# EDU_High-Speed-Design_Connectors.net
KiCad netlist of a schematic drawn in Altium Designer
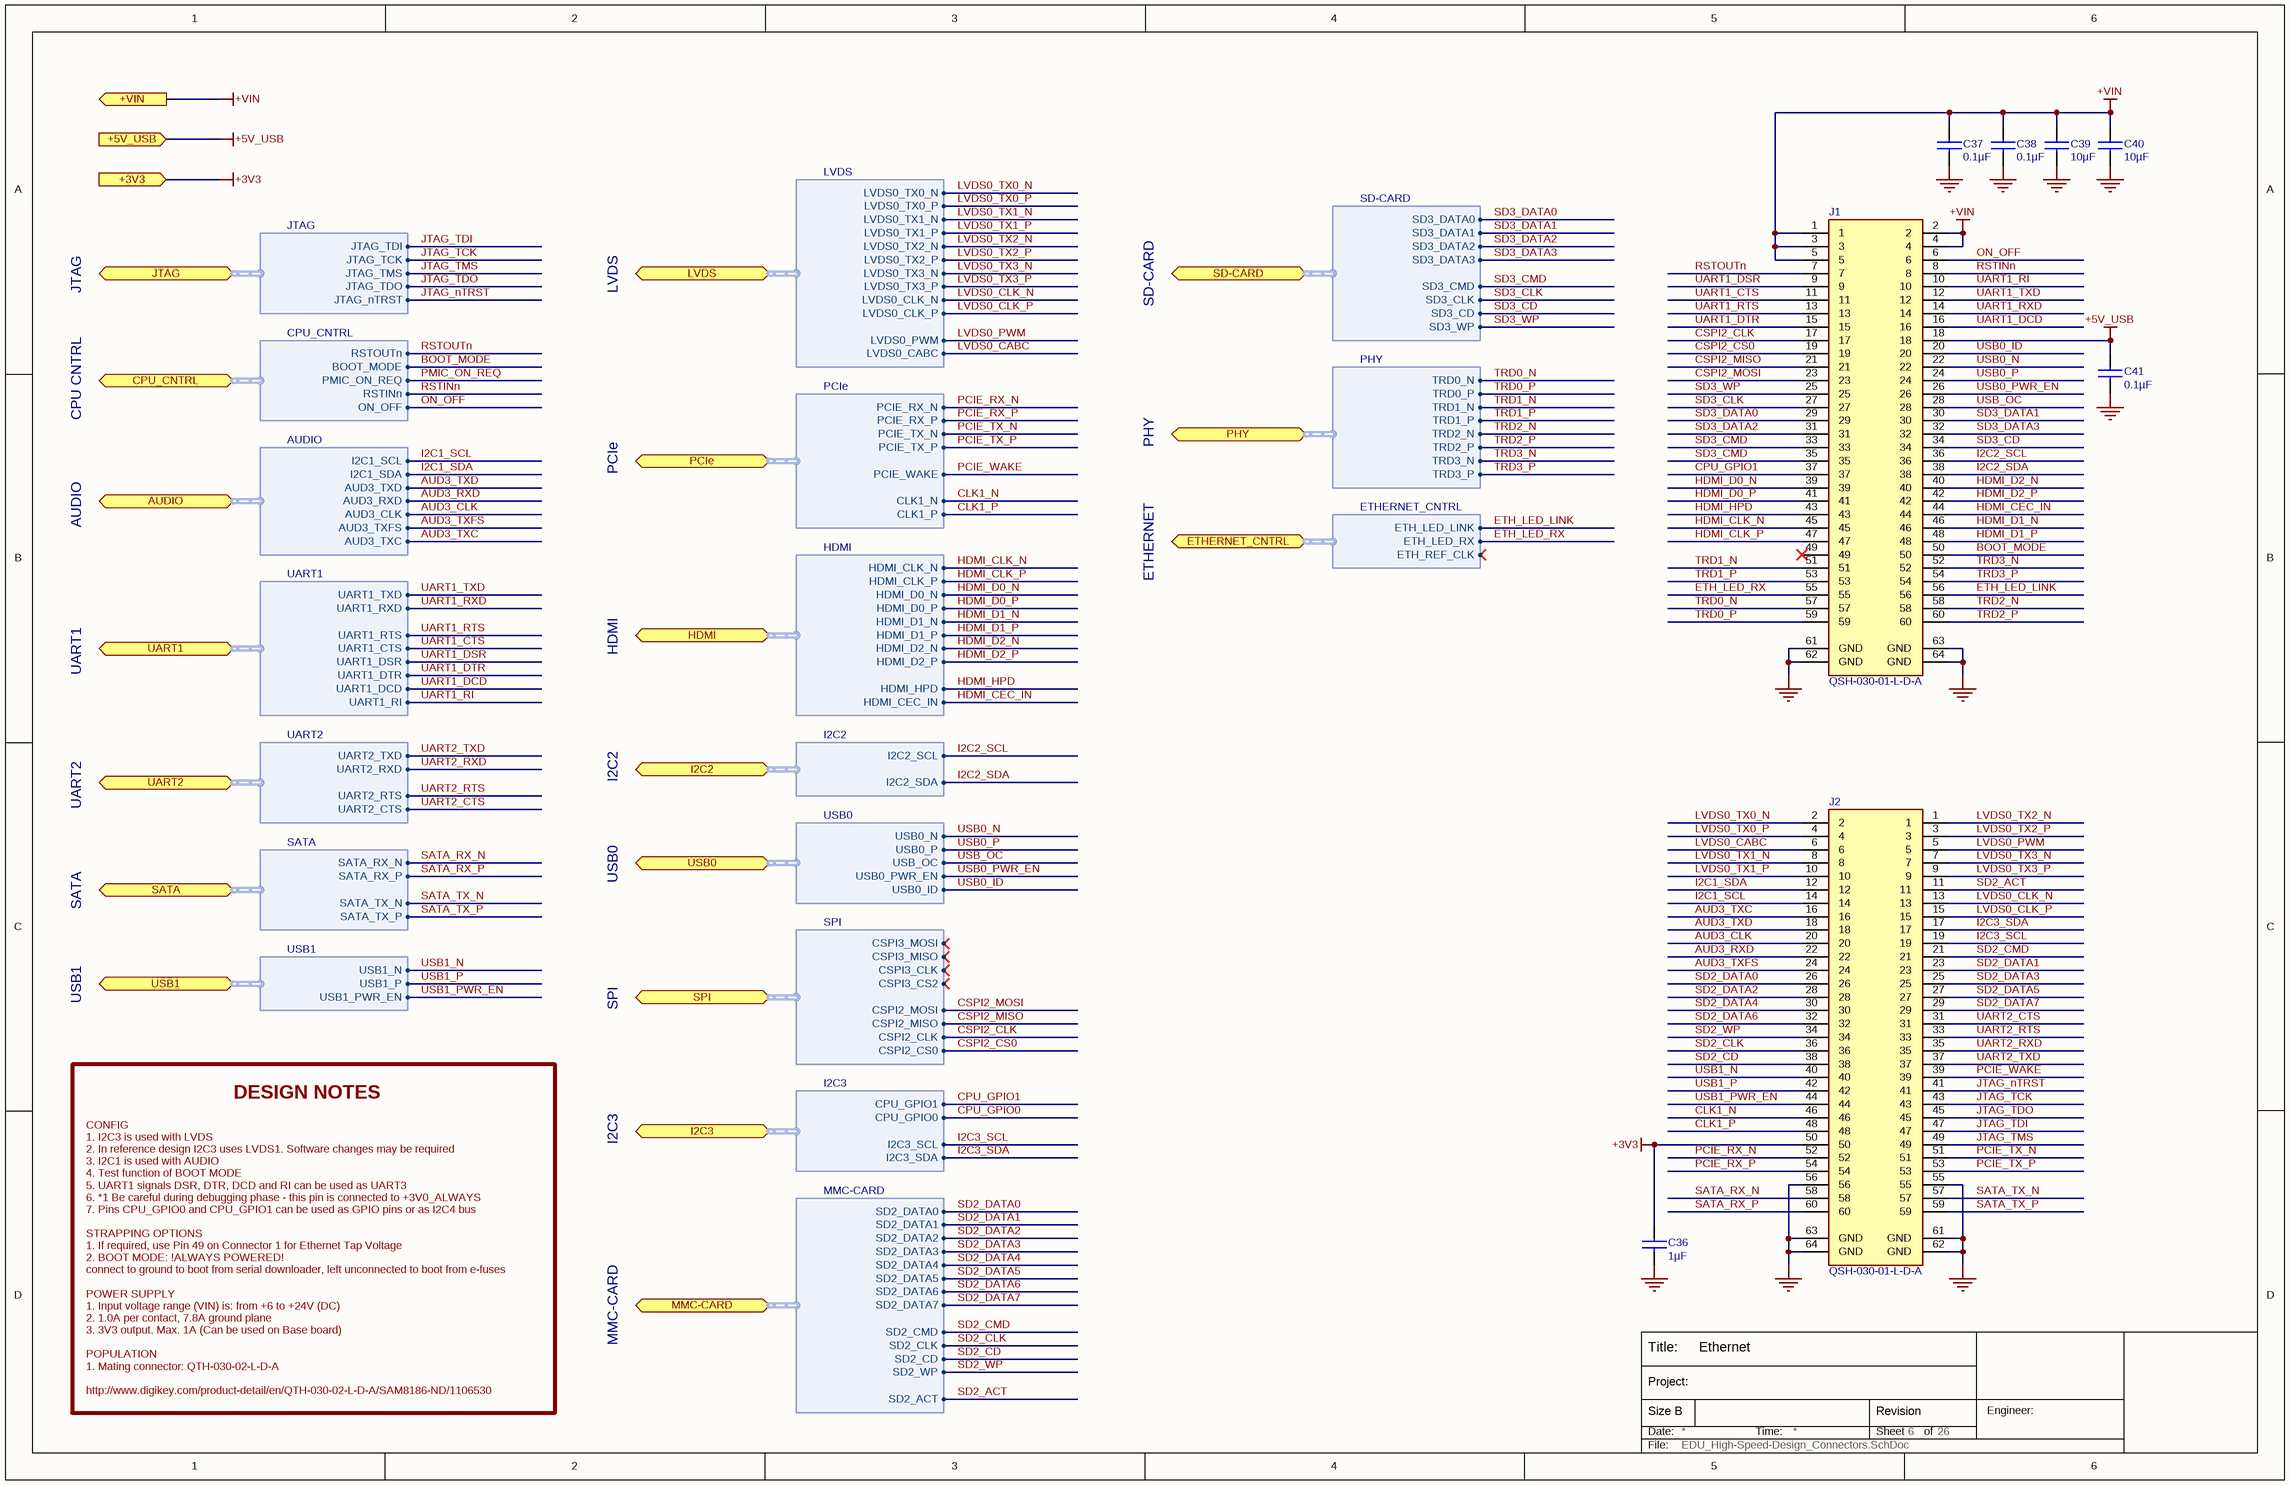
[diagram p0: EDU_High-Speed-Design_Connectors.SchDoc]

(export (version "E")
  (design (tool "Eeschema 10.0.6"))
  (components
    (comp (ref "C36")
      (value "1µF")
      (footprint "C0402")
      (description "CAP CER 1.0UF 16V X5R 0402")
      (fields (field (name "VOLTAGE") "16V"))
      (libsource (lib "EDU_High-Speed-Design") (part "C1005X5R1C105K"))
    )
    (comp (ref "C37")
      (value "0.1µF")
      (footprint "C0402")
      (description "CAP CER .10UF 50V X5R 10% 0402")
      (fields (field (name "VOLTAGE") "50V"))
      (libsource (lib "EDU_High-Speed-Design") (part "C1005X5R1H104K"))
    )
    (comp (ref "C38")
      (value "0.1µF")
      (footprint "C0402")
      (description "CAP CER .10UF 50V X5R 10% 0402")
      (fields (field (name "VOLTAGE") "50V"))
      (libsource (lib "EDU_High-Speed-Design") (part "C1005X5R1H104K"))
    )
    (comp (ref "C39")
      (value "10µF")
      (footprint "C1206")
      (description "CAP CER 10UF 35V X5R 1206")
      (fields (field (name "VOLTAGE") "35V"))
      (libsource (lib "EDU_High-Speed-Design") (part "GRM31CR6YA106KA12L"))
    )
    (comp (ref "C40")
      (value "10µF")
      (footprint "C1206")
      (description "CAP CER 10UF 35V X5R 1206")
      (fields (field (name "VOLTAGE") "35V"))
      (libsource (lib "EDU_High-Speed-Design") (part "GRM31CR6YA106KA12L"))
    )
    (comp (ref "C41")
      (value "0.1µF")
      (footprint "C0402")
      (description "CAP CER .10UF 50V X5R 10% 0402")
      (fields (field (name "VOLTAGE") "50V"))
      (libsource (lib "EDU_High-Speed-Design") (part "C1005X5R1H104K"))
    )
    (comp (ref "J1")
      (value "QSH-030-01-L-D-A")
      (footprint "QSH-030-01-L-D-A")
      (description "CONN RCPT HI-SPD .5MM 60POS DL")
      (libsource (lib "") (part "QSH-030-01-L-D-A_1"))
    )
    (comp (ref "J2")
      (value "QSH-030-01-L-D-A")
      (footprint "QSH-030-01-L-D-A")
      (description "CONN RCPT HI-SPD .5MM 60POS DL")
      (libsource (lib "EDU_High-Speed-Design") (part "QSH-030-01-L-D-A"))
    )
  )
  (nets
    (net (code "19") (name "+3V3") (class "Default")
      (node (ref "C36") (pin "1") (pinfunction "1_1") (pintype "passive"))
      (node (ref "J2") (pin "50") (pinfunction "50_50") (pintype "passive"))
    )
    (net (code "20") (name "+5V_USB") (class "Default")
      (node (ref "C41") (pin "1") (pinfunction "1_1") (pintype "passive"))
      (node (ref "J1") (pin "18") (pinfunction "18_18") (pintype "passive"))
    )
    (net (code "21") (name "+VIN") (class "Default")
      (node (ref "C37") (pin "1") (pinfunction "1_1") (pintype "passive"))
      (node (ref "C38") (pin "1") (pinfunction "1_1") (pintype "passive"))
      (node (ref "C39") (pin "1") (pinfunction "1_1") (pintype "passive"))
      (node (ref "C40") (pin "1") (pinfunction "1_1") (pintype "passive"))
      (node (ref "J1") (pin "1") (pinfunction "1_1") (pintype "passive"))
      (node (ref "J1") (pin "2") (pinfunction "2_2") (pintype "passive"))
      (node (ref "J1") (pin "3") (pinfunction "3_3") (pintype "passive"))
      (node (ref "J1") (pin "4") (pinfunction "4_4") (pintype "passive"))
      (node (ref "J1") (pin "5") (pinfunction "5_5") (pintype "passive"))
    )
    (net (code "22") (name "/AUD3_CLK") (class "Default")
      (node (ref "J2") (pin "20") (pinfunction "20_20") (pintype "passive"))
    )
    (net (code "23") (name "/AUD3_RXD") (class "Default")
      (node (ref "J2") (pin "22") (pinfunction "22_22") (pintype "passive"))
    )
    (net (code "24") (name "/AUD3_TXC") (class "Default")
      (node (ref "J2") (pin "16") (pinfunction "16_16") (pintype "passive"))
    )
    (net (code "25") (name "/AUD3_TXD") (class "Default")
      (node (ref "J2") (pin "18") (pinfunction "18_18") (pintype "passive"))
    )
    (net (code "26") (name "/AUD3_TXFS") (class "Default")
      (node (ref "J2") (pin "24") (pinfunction "24_24") (pintype "passive"))
    )
    (net (code "27") (name "/BOOT_MODE") (class "Default")
      (node (ref "J1") (pin "50") (pinfunction "50_50") (pintype "passive"))
    )
    (net (code "28") (name "/CLK1_N") (class "Default")
      (node (ref "J2") (pin "46") (pinfunction "46_46") (pintype "passive"))
    )
    (net (code "29") (name "/CLK1_P") (class "Default")
      (node (ref "J2") (pin "48") (pinfunction "48_48") (pintype "passive"))
    )
    (net (code "31") (name "/CPU_GPIO1") (class "Default")
      (node (ref "J1") (pin "37") (pinfunction "37_37") (pintype "passive"))
    )
    (net (code "32") (name "/CSPI2_CLK") (class "Default")
      (node (ref "J1") (pin "17") (pinfunction "17_17") (pintype "passive"))
    )
    (net (code "33") (name "/CSPI2_CS0") (class "Default")
      (node (ref "J1") (pin "19") (pinfunction "19_19") (pintype "passive"))
    )
    (net (code "34") (name "/CSPI2_MISO") (class "Default")
      (node (ref "J1") (pin "21") (pinfunction "21_21") (pintype "passive"))
    )
    (net (code "35") (name "/CSPI2_MOSI") (class "Default")
      (node (ref "J1") (pin "23") (pinfunction "23_23") (pintype "passive"))
    )
    (net (code "36") (name "/ETH_LED_LINK") (class "Default")
      (node (ref "J1") (pin "56") (pinfunction "56_56") (pintype "passive"))
    )
    (net (code "37") (name "/ETH_LED_RX") (class "Default")
      (node (ref "J1") (pin "55") (pinfunction "55_55") (pintype "passive"))
    )
    (net (code "38") (name "/HDMI_CEC_IN") (class "Default")
      (node (ref "J1") (pin "44") (pinfunction "44_44") (pintype "passive"))
    )
    (net (code "39") (name "/HDMI_CLK_N") (class "Default")
      (node (ref "J1") (pin "45") (pinfunction "45_45") (pintype "passive"))
    )
    (net (code "40") (name "/HDMI_CLK_P") (class "Default")
      (node (ref "J1") (pin "47") (pinfunction "47_47") (pintype "passive"))
    )
    (net (code "41") (name "/HDMI_D0_N") (class "Default")
      (node (ref "J1") (pin "39") (pinfunction "39_39") (pintype "passive"))
    )
    (net (code "42") (name "/HDMI_D0_P") (class "Default")
      (node (ref "J1") (pin "41") (pinfunction "41_41") (pintype "passive"))
    )
    (net (code "43") (name "/HDMI_D1_N") (class "Default")
      (node (ref "J1") (pin "46") (pinfunction "46_46") (pintype "passive"))
    )
    (net (code "44") (name "/HDMI_D1_P") (class "Default")
      (node (ref "J1") (pin "48") (pinfunction "48_48") (pintype "passive"))
    )
    (net (code "45") (name "/HDMI_D2_N") (class "Default")
      (node (ref "J1") (pin "40") (pinfunction "40_40") (pintype "passive"))
    )
    (net (code "46") (name "/HDMI_D2_P") (class "Default")
      (node (ref "J1") (pin "42") (pinfunction "42_42") (pintype "passive"))
    )
    (net (code "47") (name "/HDMI_HPD") (class "Default")
      (node (ref "J1") (pin "43") (pinfunction "43_43") (pintype "passive"))
    )
    (net (code "48") (name "/I2C1_SCL") (class "Default")
      (node (ref "J2") (pin "14") (pinfunction "14_14") (pintype "passive"))
    )
    (net (code "49") (name "/I2C1_SDA") (class "Default")
      (node (ref "J2") (pin "12") (pinfunction "12_12") (pintype "passive"))
    )
    (net (code "50") (name "/I2C2_SCL") (class "Default")
      (node (ref "J1") (pin "36") (pinfunction "36_36") (pintype "passive"))
    )
    (net (code "51") (name "/I2C2_SDA") (class "Default")
      (node (ref "J1") (pin "38") (pinfunction "38_38") (pintype "passive"))
    )
    (net (code "52") (name "/I2C3_SCL") (class "Default")
      (node (ref "J2") (pin "19") (pinfunction "19_19") (pintype "passive"))
    )
    (net (code "53") (name "/I2C3_SDA") (class "Default")
      (node (ref "J2") (pin "17") (pinfunction "17_17") (pintype "passive"))
    )
    (net (code "54") (name "/JTAG_TCK") (class "Default")
      (node (ref "J2") (pin "43") (pinfunction "43_43") (pintype "passive"))
    )
    (net (code "55") (name "/JTAG_TDI") (class "Default")
      (node (ref "J2") (pin "47") (pinfunction "47_47") (pintype "passive"))
    )
    (net (code "56") (name "/JTAG_TDO") (class "Default")
      (node (ref "J2") (pin "45") (pinfunction "45_45") (pintype "passive"))
    )
    (net (code "57") (name "/JTAG_TMS") (class "Default")
      (node (ref "J2") (pin "49") (pinfunction "49_49") (pintype "passive"))
    )
    (net (code "58") (name "/JTAG_nTRST") (class "Default")
      (node (ref "J2") (pin "41") (pinfunction "41_41") (pintype "passive"))
    )
    (net (code "59") (name "/LVDS0_CABC") (class "Default")
      (node (ref "J2") (pin "6") (pinfunction "6_6") (pintype "passive"))
    )
    (net (code "60") (name "/LVDS0_CLK_N") (class "Default")
      (node (ref "J2") (pin "13") (pinfunction "13_13") (pintype "passive"))
    )
    (net (code "61") (name "/LVDS0_CLK_P") (class "Default")
      (node (ref "J2") (pin "15") (pinfunction "15_15") (pintype "passive"))
    )
    (net (code "62") (name "/LVDS0_PWM") (class "Default")
      (node (ref "J2") (pin "5") (pinfunction "5_5") (pintype "passive"))
    )
    (net (code "63") (name "/LVDS0_TX0_N") (class "Default")
      (node (ref "J2") (pin "2") (pinfunction "2_2") (pintype "passive"))
    )
    (net (code "64") (name "/LVDS0_TX0_P") (class "Default")
      (node (ref "J2") (pin "4") (pinfunction "4_4") (pintype "passive"))
    )
    (net (code "65") (name "/LVDS0_TX1_N") (class "Default")
      (node (ref "J2") (pin "8") (pinfunction "8_8") (pintype "passive"))
    )
    (net (code "66") (name "/LVDS0_TX1_P") (class "Default")
      (node (ref "J2") (pin "10") (pinfunction "10_10") (pintype "passive"))
    )
    (net (code "67") (name "/LVDS0_TX2_N") (class "Default")
      (node (ref "J2") (pin "1") (pinfunction "1_1") (pintype "passive"))
    )
    (net (code "68") (name "/LVDS0_TX2_P") (class "Default")
      (node (ref "J2") (pin "3") (pinfunction "3_3") (pintype "passive"))
    )
    (net (code "69") (name "/LVDS0_TX3_N") (class "Default")
      (node (ref "J2") (pin "7") (pinfunction "7_7") (pintype "passive"))
    )
    (net (code "70") (name "/LVDS0_TX3_P") (class "Default")
      (node (ref "J2") (pin "9") (pinfunction "9_9") (pintype "passive"))
    )
    (net (code "71") (name "/ON_OFF") (class "Default")
      (node (ref "J1") (pin "6") (pinfunction "6_6") (pintype "passive"))
    )
    (net (code "72") (name "/PCIE_RX_N") (class "Default")
      (node (ref "J2") (pin "52") (pinfunction "52_52") (pintype "passive"))
    )
    (net (code "73") (name "/PCIE_RX_P") (class "Default")
      (node (ref "J2") (pin "54") (pinfunction "54_54") (pintype "passive"))
    )
    (net (code "74") (name "/PCIE_TX_N") (class "Default")
      (node (ref "J2") (pin "51") (pinfunction "51_51") (pintype "passive"))
    )
    (net (code "75") (name "/PCIE_TX_P") (class "Default")
      (node (ref "J2") (pin "53") (pinfunction "53_53") (pintype "passive"))
    )
    (net (code "76") (name "/PCIE_WAKE") (class "Default")
      (node (ref "J2") (pin "39") (pinfunction "39_39") (pintype "passive"))
    )
    (net (code "78") (name "/RSTINn") (class "Default")
      (node (ref "J1") (pin "8") (pinfunction "8_8") (pintype "passive"))
    )
    (net (code "79") (name "/RSTOUTn") (class "Default")
      (node (ref "J1") (pin "7") (pinfunction "7_7") (pintype "passive"))
    )
    (net (code "80") (name "/SATA_RX_N") (class "Default")
      (node (ref "J2") (pin "58") (pinfunction "58_58") (pintype "passive"))
    )
    (net (code "81") (name "/SATA_RX_P") (class "Default")
      (node (ref "J2") (pin "60") (pinfunction "60_60") (pintype "passive"))
    )
    (net (code "82") (name "/SATA_TX_N") (class "Default")
      (node (ref "J2") (pin "57") (pinfunction "57_57") (pintype "passive"))
    )
    (net (code "83") (name "/SATA_TX_P") (class "Default")
      (node (ref "J2") (pin "59") (pinfunction "59_59") (pintype "passive"))
    )
    (net (code "84") (name "/SD2_ACT") (class "Default")
      (node (ref "J2") (pin "11") (pinfunction "11_11") (pintype "passive"))
    )
    (net (code "85") (name "/SD2_CD") (class "Default")
      (node (ref "J2") (pin "38") (pinfunction "38_38") (pintype "passive"))
    )
    (net (code "86") (name "/SD2_CLK") (class "Default")
      (node (ref "J2") (pin "36") (pinfunction "36_36") (pintype "passive"))
    )
    (net (code "87") (name "/SD2_CMD") (class "Default")
      (node (ref "J2") (pin "21") (pinfunction "21_21") (pintype "passive"))
    )
    (net (code "88") (name "/SD2_DATA0") (class "Default")
      (node (ref "J2") (pin "26") (pinfunction "26_26") (pintype "passive"))
    )
    (net (code "89") (name "/SD2_DATA1") (class "Default")
      (node (ref "J2") (pin "23") (pinfunction "23_23") (pintype "passive"))
    )
    (net (code "90") (name "/SD2_DATA2") (class "Default")
      (node (ref "J2") (pin "28") (pinfunction "28_28") (pintype "passive"))
    )
    (net (code "91") (name "/SD2_DATA3") (class "Default")
      (node (ref "J2") (pin "25") (pinfunction "25_25") (pintype "passive"))
    )
    (net (code "92") (name "/SD2_DATA4") (class "Default")
      (node (ref "J2") (pin "30") (pinfunction "30_30") (pintype "passive"))
    )
    (net (code "93") (name "/SD2_DATA5") (class "Default")
      (node (ref "J2") (pin "27") (pinfunction "27_27") (pintype "passive"))
    )
    (net (code "94") (name "/SD2_DATA6") (class "Default")
      (node (ref "J2") (pin "32") (pinfunction "32_32") (pintype "passive"))
    )
    (net (code "95") (name "/SD2_DATA7") (class "Default")
      (node (ref "J2") (pin "29") (pinfunction "29_29") (pintype "passive"))
    )
    (net (code "96") (name "/SD2_WP") (class "Default")
      (node (ref "J2") (pin "34") (pinfunction "34_34") (pintype "passive"))
    )
    (net (code "97") (name "/SD3_CD") (class "Default")
      (node (ref "J1") (pin "34") (pinfunction "34_34") (pintype "passive"))
    )
    (net (code "98") (name "/SD3_CLK") (class "Default")
      (node (ref "J1") (pin "27") (pinfunction "27_27") (pintype "passive"))
    )
    (net (code "99") (name "/SD3_CMD") (class "Default")
      (node (ref "J1") (pin "33") (pinfunction "33_33") (pintype "passive"))
      (node (ref "J1") (pin "35") (pinfunction "35_35") (pintype "passive"))
    )
    (net (code "100") (name "/SD3_DATA0") (class "Default")
      (node (ref "J1") (pin "29") (pinfunction "29_29") (pintype "passive"))
    )
    (net (code "101") (name "/SD3_DATA1") (class "Default")
      (node (ref "J1") (pin "30") (pinfunction "30_30") (pintype "passive"))
    )
    (net (code "102") (name "/SD3_DATA2") (class "Default")
      (node (ref "J1") (pin "31") (pinfunction "31_31") (pintype "passive"))
    )
    (net (code "103") (name "/SD3_DATA3") (class "Default")
      (node (ref "J1") (pin "32") (pinfunction "32_32") (pintype "passive"))
    )
    (net (code "104") (name "/SD3_WP") (class "Default")
      (node (ref "J1") (pin "25") (pinfunction "25_25") (pintype "passive"))
    )
    (net (code "105") (name "/TRD0_N") (class "Default")
      (node (ref "J1") (pin "57") (pinfunction "57_57") (pintype "passive"))
    )
    (net (code "106") (name "/TRD0_P") (class "Default")
      (node (ref "J1") (pin "59") (pinfunction "59_59") (pintype "passive"))
    )
    (net (code "107") (name "/TRD1_N") (class "Default")
      (node (ref "J1") (pin "51") (pinfunction "51_51") (pintype "passive"))
    )
    (net (code "108") (name "/TRD1_P") (class "Default")
      (node (ref "J1") (pin "53") (pinfunction "53_53") (pintype "passive"))
    )
    (net (code "109") (name "/TRD2_N") (class "Default")
      (node (ref "J1") (pin "58") (pinfunction "58_58") (pintype "passive"))
    )
    (net (code "110") (name "/TRD2_P") (class "Default")
      (node (ref "J1") (pin "60") (pinfunction "60_60") (pintype "passive"))
    )
    (net (code "111") (name "/TRD3_N") (class "Default")
      (node (ref "J1") (pin "52") (pinfunction "52_52") (pintype "passive"))
    )
    (net (code "112") (name "/TRD3_P") (class "Default")
      (node (ref "J1") (pin "54") (pinfunction "54_54") (pintype "passive"))
    )
    (net (code "113") (name "/UART1_CTS") (class "Default")
      (node (ref "J1") (pin "11") (pinfunction "11_11") (pintype "passive"))
    )
    (net (code "114") (name "/UART1_DCD") (class "Default")
      (node (ref "J1") (pin "16") (pinfunction "16_16") (pintype "passive"))
    )
    (net (code "115") (name "/UART1_DSR") (class "Default")
      (node (ref "J1") (pin "9") (pinfunction "9_9") (pintype "passive"))
    )
    (net (code "116") (name "/UART1_DTR") (class "Default")
      (node (ref "J1") (pin "15") (pinfunction "15_15") (pintype "passive"))
    )
    (net (code "117") (name "/UART1_RI") (class "Default")
      (node (ref "J1") (pin "10") (pinfunction "10_10") (pintype "passive"))
    )
    (net (code "118") (name "/UART1_RTS") (class "Default")
      (node (ref "J1") (pin "13") (pinfunction "13_13") (pintype "passive"))
    )
    (net (code "119") (name "/UART1_RXD") (class "Default")
      (node (ref "J1") (pin "14") (pinfunction "14_14") (pintype "passive"))
    )
    (net (code "120") (name "/UART1_TXD") (class "Default")
      (node (ref "J1") (pin "12") (pinfunction "12_12") (pintype "passive"))
    )
    (net (code "121") (name "/UART2_CTS") (class "Default")
      (node (ref "J2") (pin "31") (pinfunction "31_31") (pintype "passive"))
    )
    (net (code "122") (name "/UART2_RTS") (class "Default")
      (node (ref "J2") (pin "33") (pinfunction "33_33") (pintype "passive"))
    )
    (net (code "123") (name "/UART2_RXD") (class "Default")
      (node (ref "J2") (pin "35") (pinfunction "35_35") (pintype "passive"))
    )
    (net (code "124") (name "/UART2_TXD") (class "Default")
      (node (ref "J2") (pin "37") (pinfunction "37_37") (pintype "passive"))
    )
    (net (code "125") (name "/USB0_ID") (class "Default")
      (node (ref "J1") (pin "20") (pinfunction "20_20") (pintype "passive"))
    )
    (net (code "126") (name "/USB0_N") (class "Default")
      (node (ref "J1") (pin "22") (pinfunction "22_22") (pintype "passive"))
    )
    (net (code "127") (name "/USB0_P") (class "Default")
      (node (ref "J1") (pin "24") (pinfunction "24_24") (pintype "passive"))
    )
    (net (code "128") (name "/USB0_PWR_EN") (class "Default")
      (node (ref "J1") (pin "26") (pinfunction "26_26") (pintype "passive"))
    )
    (net (code "129") (name "/USB1_N") (class "Default")
      (node (ref "J2") (pin "40") (pinfunction "40_40") (pintype "passive"))
    )
    (net (code "130") (name "/USB1_P") (class "Default")
      (node (ref "J2") (pin "42") (pinfunction "42_42") (pintype "passive"))
    )
    (net (code "131") (name "/USB1_PWR_EN") (class "Default")
      (node (ref "J2") (pin "44") (pinfunction "44_44") (pintype "passive"))
    )
    (net (code "132") (name "/USB_OC") (class "Default")
      (node (ref "J1") (pin "28") (pinfunction "28_28") (pintype "passive"))
    )
    (net (code "151") (name "GND") (class "Default")
      (node (ref "C36") (pin "2") (pinfunction "2_2") (pintype "passive"))
      (node (ref "C37") (pin "2") (pinfunction "2_2") (pintype "passive"))
      (node (ref "C38") (pin "2") (pinfunction "2_2") (pintype "passive"))
      (node (ref "C39") (pin "2") (pinfunction "2_2") (pintype "passive"))
      (node (ref "C40") (pin "2") (pinfunction "2_2") (pintype "passive"))
      (node (ref "C41") (pin "2") (pinfunction "2_2") (pintype "passive"))
      (node (ref "J1") (pin "61") (pinfunction "GND_61") (pintype "passive"))
      (node (ref "J1") (pin "62") (pinfunction "GND_62") (pintype "passive"))
      (node (ref "J1") (pin "63") (pinfunction "GND_63") (pintype "passive"))
      (node (ref "J1") (pin "64") (pinfunction "GND_64") (pintype "passive"))
      (node (ref "J2") (pin "55") (pinfunction "55_55") (pintype "passive"))
      (node (ref "J2") (pin "56") (pinfunction "56_56") (pintype "passive"))
      (node (ref "J2") (pin "61") (pinfunction "GND_61") (pintype "passive"))
      (node (ref "J2") (pin "62") (pinfunction "GND_62") (pintype "passive"))
      (node (ref "J2") (pin "63") (pinfunction "GND_63") (pintype "passive"))
      (node (ref "J2") (pin "64") (pinfunction "GND_64") (pintype "passive"))
    )
    (net (code "152") (name "unconnected-(J1-HOLE1-Pad65)") (class "Default")
      (node (ref "J1") (pin "65") (pinfunction "HOLE1_65") (pintype "passive"))
    )
    (net (code "153") (name "unconnected-(J1-HOLE2-Pad66)") (class "Default")
      (node (ref "J1") (pin "66") (pinfunction "HOLE2_66") (pintype "passive"))
    )
    (net (code "154") (name "unconnected-(J1-Pad49)") (class "Default")
      (node (ref "J1") (pin "49") (pinfunction "49_49") (pintype "passive+no_connect"))
    )
    (net (code "155") (name "unconnected-(J2-HOLE1-Pad65)") (class "Default")
      (node (ref "J2") (pin "65") (pinfunction "HOLE1_65") (pintype "passive"))
    )
    (net (code "156") (name "unconnected-(J2-HOLE2-Pad66)") (class "Default")
      (node (ref "J2") (pin "66") (pinfunction "HOLE2_66") (pintype "passive"))
    )
  )
)
